# base-6u-custom-8535.net
KiCad netlist of a schematic drawn in EAGLE
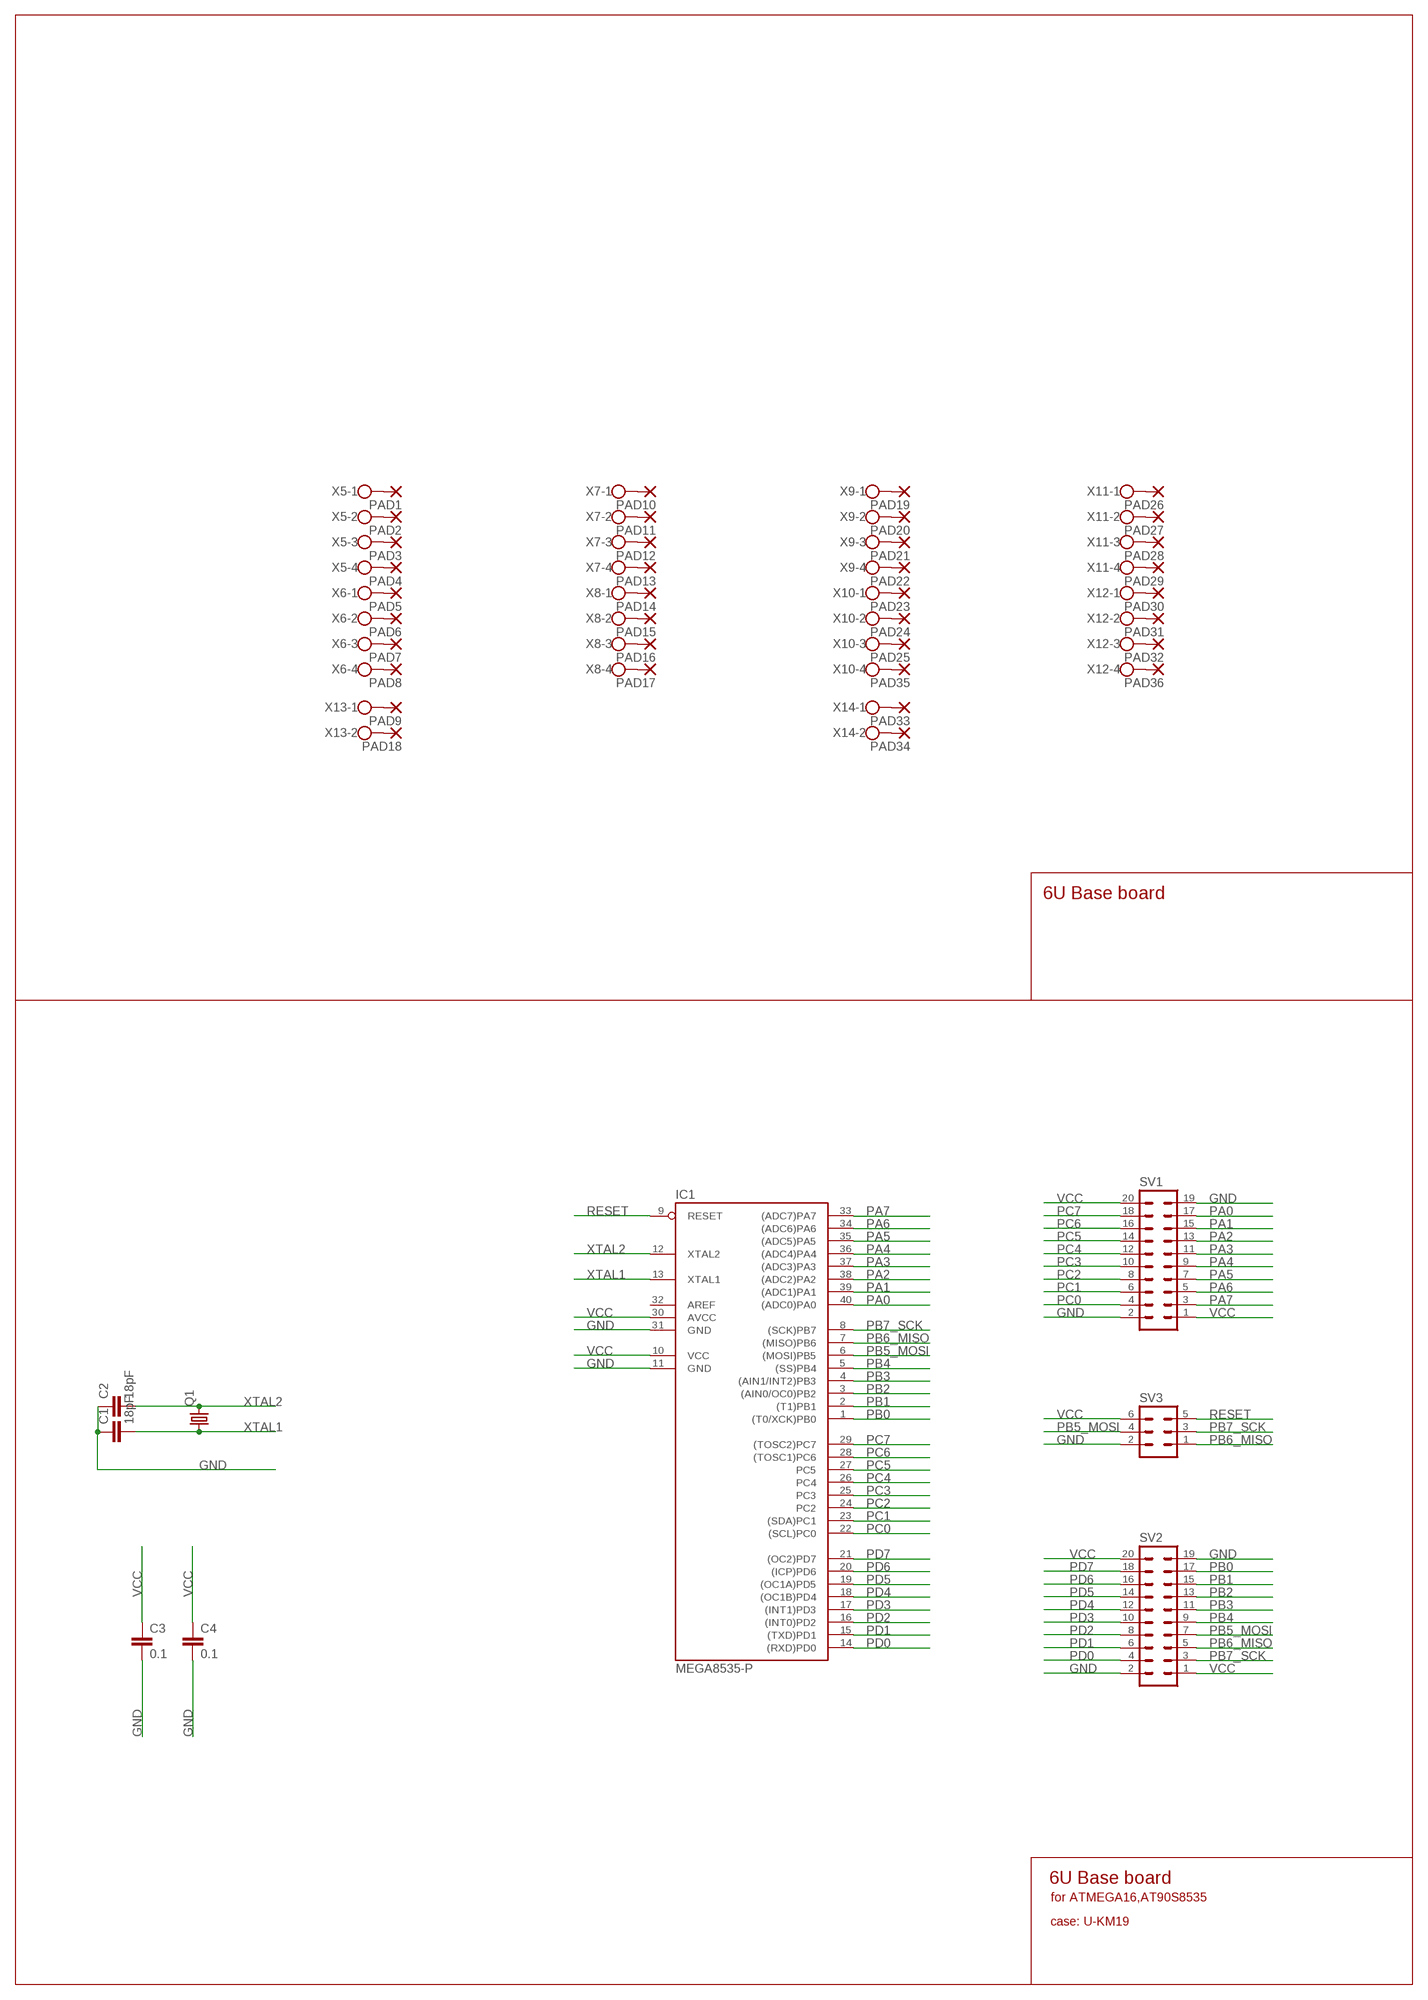
[diagram p0: schematic, sheet 1]

(export (version "E")
  (design (tool "Eeschema 10.0.6"))
  (components
    (comp (ref "C1")
      (value "18pF")
      (footprint "eagle-import:C0805")
      (libsource (lib "eagle-import") (part "C-EUC0805"))
    )
    (comp (ref "C2")
      (value "18pF")
      (footprint "eagle-import:C0805")
      (libsource (lib "eagle-import") (part "C-EUC0805"))
    )
    (comp (ref "C3")
      (value "0.1")
      (footprint "eagle-import:C0805")
      (libsource (lib "eagle-import") (part "C-EUC0805"))
    )
    (comp (ref "C4")
      (value "0.1")
      (footprint "eagle-import:C0805")
      (libsource (lib "eagle-import") (part "C-EUC0805"))
    )
    (comp (ref "IC1")
      (value "MEGA8535-P")
      (footprint "eagle-import:DIL40")
      (fields (field (name "MPN") "ATMEGA8535-16PU"))
      (libsource (lib "eagle-import") (part "MEGA8535-P"))
    )
    (comp (ref "PAD1")
      (value "2,54/0,8")
      (footprint "eagle-import:2,54_0,8")
      (libsource (lib "eagle-import") (part "2,54/0,8"))
    )
    (comp (ref "PAD2")
      (value "2,54/0,8")
      (footprint "eagle-import:2,54_0,8")
      (libsource (lib "eagle-import") (part "2,54/0,8"))
    )
    (comp (ref "PAD3")
      (value "2,54/0,8")
      (footprint "eagle-import:2,54_0,8")
      (libsource (lib "eagle-import") (part "2,54/0,8"))
    )
    (comp (ref "PAD4")
      (value "2,54/0,8")
      (footprint "eagle-import:2,54_0,8")
      (libsource (lib "eagle-import") (part "2,54/0,8"))
    )
    (comp (ref "PAD5")
      (value "2,54/0,8")
      (footprint "eagle-import:2,54_0,8")
      (libsource (lib "eagle-import") (part "2,54/0,8"))
    )
    (comp (ref "PAD6")
      (value "2,54/0,8")
      (footprint "eagle-import:2,54_0,8")
      (libsource (lib "eagle-import") (part "2,54/0,8"))
    )
    (comp (ref "PAD7")
      (value "2,54/0,8")
      (footprint "eagle-import:2,54_0,8")
      (libsource (lib "eagle-import") (part "2,54/0,8"))
    )
    (comp (ref "PAD8")
      (value "2,54/0,8")
      (footprint "eagle-import:2,54_0,8")
      (libsource (lib "eagle-import") (part "2,54/0,8"))
    )
    (comp (ref "PAD9")
      (value "2,54/0,8")
      (footprint "eagle-import:2,54_0,8")
      (libsource (lib "eagle-import") (part "2,54/0,8"))
    )
    (comp (ref "PAD10")
      (value "2,54/0,8")
      (footprint "eagle-import:2,54_0,8")
      (libsource (lib "eagle-import") (part "2,54/0,8"))
    )
    (comp (ref "PAD11")
      (value "2,54/0,8")
      (footprint "eagle-import:2,54_0,8")
      (libsource (lib "eagle-import") (part "2,54/0,8"))
    )
    (comp (ref "PAD12")
      (value "2,54/0,8")
      (footprint "eagle-import:2,54_0,8")
      (libsource (lib "eagle-import") (part "2,54/0,8"))
    )
    (comp (ref "PAD13")
      (value "2,54/0,8")
      (footprint "eagle-import:2,54_0,8")
      (libsource (lib "eagle-import") (part "2,54/0,8"))
    )
    (comp (ref "PAD14")
      (value "2,54/0,8")
      (footprint "eagle-import:2,54_0,8")
      (libsource (lib "eagle-import") (part "2,54/0,8"))
    )
    (comp (ref "PAD15")
      (value "2,54/0,8")
      (footprint "eagle-import:2,54_0,8")
      (libsource (lib "eagle-import") (part "2,54/0,8"))
    )
    (comp (ref "PAD16")
      (value "2,54/0,8")
      (footprint "eagle-import:2,54_0,8")
      (libsource (lib "eagle-import") (part "2,54/0,8"))
    )
    (comp (ref "PAD17")
      (value "2,54/0,8")
      (footprint "eagle-import:2,54_0,8")
      (libsource (lib "eagle-import") (part "2,54/0,8"))
    )
    (comp (ref "PAD18")
      (value "2,54/0,8")
      (footprint "eagle-import:2,54_0,8")
      (libsource (lib "eagle-import") (part "2,54/0,8"))
    )
    (comp (ref "PAD19")
      (value "2,54/0,8")
      (footprint "eagle-import:2,54_0,8")
      (libsource (lib "eagle-import") (part "2,54/0,8"))
    )
    (comp (ref "PAD20")
      (value "2,54/0,8")
      (footprint "eagle-import:2,54_0,8")
      (libsource (lib "eagle-import") (part "2,54/0,8"))
    )
    (comp (ref "PAD21")
      (value "2,54/0,8")
      (footprint "eagle-import:2,54_0,8")
      (libsource (lib "eagle-import") (part "2,54/0,8"))
    )
    (comp (ref "PAD22")
      (value "2,54/0,8")
      (footprint "eagle-import:2,54_0,8")
      (libsource (lib "eagle-import") (part "2,54/0,8"))
    )
    (comp (ref "PAD23")
      (value "2,54/0,8")
      (footprint "eagle-import:2,54_0,8")
      (libsource (lib "eagle-import") (part "2,54/0,8"))
    )
    (comp (ref "PAD24")
      (value "2,54/0,8")
      (footprint "eagle-import:2,54_0,8")
      (libsource (lib "eagle-import") (part "2,54/0,8"))
    )
    (comp (ref "PAD25")
      (value "2,54/0,8")
      (footprint "eagle-import:2,54_0,8")
      (libsource (lib "eagle-import") (part "2,54/0,8"))
    )
    (comp (ref "PAD26")
      (value "2,54/0,8")
      (footprint "eagle-import:2,54_0,8")
      (libsource (lib "eagle-import") (part "2,54/0,8"))
    )
    (comp (ref "PAD27")
      (value "2,54/0,8")
      (footprint "eagle-import:2,54_0,8")
      (libsource (lib "eagle-import") (part "2,54/0,8"))
    )
    (comp (ref "PAD28")
      (value "2,54/0,8")
      (footprint "eagle-import:2,54_0,8")
      (libsource (lib "eagle-import") (part "2,54/0,8"))
    )
    (comp (ref "PAD29")
      (value "2,54/0,8")
      (footprint "eagle-import:2,54_0,8")
      (libsource (lib "eagle-import") (part "2,54/0,8"))
    )
    (comp (ref "PAD30")
      (value "2,54/0,8")
      (footprint "eagle-import:2,54_0,8")
      (libsource (lib "eagle-import") (part "2,54/0,8"))
    )
    (comp (ref "PAD31")
      (value "2,54/0,8")
      (footprint "eagle-import:2,54_0,8")
      (libsource (lib "eagle-import") (part "2,54/0,8"))
    )
    (comp (ref "PAD32")
      (value "2,54/0,8")
      (footprint "eagle-import:2,54_0,8")
      (libsource (lib "eagle-import") (part "2,54/0,8"))
    )
    (comp (ref "PAD33")
      (value "2,54/0,8")
      (footprint "eagle-import:2,54_0,8")
      (libsource (lib "eagle-import") (part "2,54/0,8"))
    )
    (comp (ref "PAD34")
      (value "2,54/0,8")
      (footprint "eagle-import:2,54_0,8")
      (libsource (lib "eagle-import") (part "2,54/0,8"))
    )
    (comp (ref "PAD35")
      (value "2,54/0,8")
      (footprint "eagle-import:2,54_0,8")
      (libsource (lib "eagle-import") (part "2,54/0,8"))
    )
    (comp (ref "PAD36")
      (value "2,54/0,8")
      (footprint "eagle-import:2,54_0,8")
      (libsource (lib "eagle-import") (part "2,54/0,8"))
    )
    (comp (ref "Q1")
      (value "CRYSTALHC49S")
      (footprint "eagle-import:HC49_S")
      (libsource (lib "eagle-import") (part "CRYSTALHC49S"))
    )
    (comp (ref "SV1")
      (value "MA10-2")
      (footprint "eagle-import:MA10-2")
      (libsource (lib "eagle-import") (part "MA10-2"))
    )
    (comp (ref "SV2")
      (value "MA10-2")
      (footprint "eagle-import:MA10-2")
      (libsource (lib "eagle-import") (part "MA10-2"))
    )
    (comp (ref "SV3")
      (value "MA03-2")
      (footprint "eagle-import:MA03-2")
      (libsource (lib "eagle-import") (part "MA03-2"))
    )
    (comp (ref "X5")
      (value "W237-4")
      (footprint "eagle-import:W237-4")
      (libsource (lib "eagle-import") (part "W237-4"))
    )
    (comp (ref "X6")
      (value "W237-4")
      (footprint "eagle-import:W237-4")
      (libsource (lib "eagle-import") (part "W237-4"))
    )
    (comp (ref "X7")
      (value "W237-4")
      (footprint "eagle-import:W237-4")
      (libsource (lib "eagle-import") (part "W237-4"))
    )
    (comp (ref "X8")
      (value "W237-4")
      (footprint "eagle-import:W237-4")
      (libsource (lib "eagle-import") (part "W237-4"))
    )
    (comp (ref "X9")
      (value "W237-4")
      (footprint "eagle-import:W237-4")
      (libsource (lib "eagle-import") (part "W237-4"))
    )
    (comp (ref "X10")
      (value "W237-4")
      (footprint "eagle-import:W237-4")
      (libsource (lib "eagle-import") (part "W237-4"))
    )
    (comp (ref "X11")
      (value "W237-4")
      (footprint "eagle-import:W237-4")
      (libsource (lib "eagle-import") (part "W237-4"))
    )
    (comp (ref "X12")
      (value "W237-4")
      (footprint "eagle-import:W237-4")
      (libsource (lib "eagle-import") (part "W237-4"))
    )
    (comp (ref "X13")
      (value "W237-102")
      (footprint "eagle-import:W237-102")
      (fields (field (name "MPN") "237-102"))
      (libsource (lib "eagle-import") (part "W237-102"))
    )
    (comp (ref "X14")
      (value "W237-102")
      (footprint "eagle-import:W237-102")
      (fields (field (name "MPN") "237-102"))
      (libsource (lib "eagle-import") (part "W237-102"))
    )
  )
  (nets
    (net (code "1") (name "/GND") (class "Default")
      (node (ref "C1") (pin "1") (pinfunction "1_1") (pintype "passive"))
      (node (ref "C2") (pin "1") (pinfunction "1_1") (pintype "passive"))
      (node (ref "C3") (pin "2") (pinfunction "2_2") (pintype "passive"))
      (node (ref "C4") (pin "2") (pinfunction "2_2") (pintype "passive"))
      (node (ref "IC1") (pin "11") (pinfunction "GND_11") (pintype "power_in"))
      (node (ref "IC1") (pin "31") (pinfunction "GND_31") (pintype "power_in"))
      (node (ref "SV1") (pin "19") (pinfunction "19_19") (pintype "passive"))
      (node (ref "SV1") (pin "2") (pinfunction "2_2") (pintype "passive"))
      (node (ref "SV2") (pin "19") (pinfunction "19_19") (pintype "passive"))
      (node (ref "SV2") (pin "2") (pinfunction "2_2") (pintype "passive"))
      (node (ref "SV3") (pin "2") (pinfunction "2_2") (pintype "passive"))
    )
    (net (code "2") (name "/PA0") (class "Default")
      (node (ref "IC1") (pin "40") (pinfunction "(ADC0)PA0_40") (pintype "bidirectional"))
      (node (ref "SV1") (pin "17") (pinfunction "17_17") (pintype "passive"))
    )
    (net (code "3") (name "/PA1") (class "Default")
      (node (ref "IC1") (pin "39") (pinfunction "(ADC1)PA1_39") (pintype "bidirectional"))
      (node (ref "SV1") (pin "15") (pinfunction "15_15") (pintype "passive"))
    )
    (net (code "4") (name "/PA2") (class "Default")
      (node (ref "IC1") (pin "38") (pinfunction "(ADC2)PA2_38") (pintype "bidirectional"))
      (node (ref "SV1") (pin "13") (pinfunction "13_13") (pintype "passive"))
    )
    (net (code "5") (name "/PA3") (class "Default")
      (node (ref "IC1") (pin "37") (pinfunction "(ADC3)PA3_37") (pintype "bidirectional"))
      (node (ref "SV1") (pin "11") (pinfunction "11_11") (pintype "passive"))
    )
    (net (code "6") (name "/PA4") (class "Default")
      (node (ref "IC1") (pin "36") (pinfunction "(ADC4)PA4_36") (pintype "bidirectional"))
      (node (ref "SV1") (pin "9") (pinfunction "9_9") (pintype "passive"))
    )
    (net (code "7") (name "/PA5") (class "Default")
      (node (ref "IC1") (pin "35") (pinfunction "(ADC5)PA5_35") (pintype "bidirectional"))
      (node (ref "SV1") (pin "7") (pinfunction "7_7") (pintype "passive"))
    )
    (net (code "8") (name "/PA6") (class "Default")
      (node (ref "IC1") (pin "34") (pinfunction "(ADC6)PA6_34") (pintype "bidirectional"))
      (node (ref "SV1") (pin "5") (pinfunction "5_5") (pintype "passive"))
    )
    (net (code "9") (name "/PA7") (class "Default")
      (node (ref "IC1") (pin "33") (pinfunction "(ADC7)PA7_33") (pintype "bidirectional"))
      (node (ref "SV1") (pin "3") (pinfunction "3_3") (pintype "passive"))
    )
    (net (code "10") (name "/PB0") (class "Default")
      (node (ref "IC1") (pin "1") (pinfunction "(T0/XCK)PB0_1") (pintype "bidirectional"))
      (node (ref "SV2") (pin "17") (pinfunction "17_17") (pintype "passive"))
    )
    (net (code "11") (name "/PB1") (class "Default")
      (node (ref "IC1") (pin "2") (pinfunction "(T1)PB1_2") (pintype "bidirectional"))
      (node (ref "SV2") (pin "15") (pinfunction "15_15") (pintype "passive"))
    )
    (net (code "12") (name "/PB2") (class "Default")
      (node (ref "IC1") (pin "3") (pinfunction "(AIN0/OC0)PB2_3") (pintype "bidirectional"))
      (node (ref "SV2") (pin "13") (pinfunction "13_13") (pintype "passive"))
    )
    (net (code "13") (name "/PB3") (class "Default")
      (node (ref "IC1") (pin "4") (pinfunction "(AIN1/INT2)PB3_4") (pintype "bidirectional"))
      (node (ref "SV2") (pin "11") (pinfunction "11_11") (pintype "passive"))
    )
    (net (code "14") (name "/PB4") (class "Default")
      (node (ref "IC1") (pin "5") (pinfunction "(SS)PB4_5") (pintype "bidirectional"))
      (node (ref "SV2") (pin "9") (pinfunction "9_9") (pintype "passive"))
    )
    (net (code "15") (name "/PB5_MOSI") (class "Default")
      (node (ref "IC1") (pin "6") (pinfunction "(MOSI)PB5_6") (pintype "bidirectional"))
      (node (ref "SV2") (pin "7") (pinfunction "7_7") (pintype "passive"))
      (node (ref "SV3") (pin "4") (pinfunction "4_4") (pintype "passive"))
    )
    (net (code "16") (name "/PB6_MISO") (class "Default")
      (node (ref "IC1") (pin "7") (pinfunction "(MISO)PB6_7") (pintype "bidirectional"))
      (node (ref "SV2") (pin "5") (pinfunction "5_5") (pintype "passive"))
      (node (ref "SV3") (pin "1") (pinfunction "1_1") (pintype "passive"))
    )
    (net (code "17") (name "/PB7_SCK") (class "Default")
      (node (ref "IC1") (pin "8") (pinfunction "(SCK)PB7_8") (pintype "bidirectional"))
      (node (ref "SV2") (pin "3") (pinfunction "3_3") (pintype "passive"))
      (node (ref "SV3") (pin "3") (pinfunction "3_3") (pintype "passive"))
    )
    (net (code "18") (name "/PC0") (class "Default")
      (node (ref "IC1") (pin "22") (pinfunction "(SCL)PC0_22") (pintype "bidirectional"))
      (node (ref "SV1") (pin "4") (pinfunction "4_4") (pintype "passive"))
    )
    (net (code "19") (name "/PC1") (class "Default")
      (node (ref "IC1") (pin "23") (pinfunction "(SDA)PC1_23") (pintype "bidirectional"))
      (node (ref "SV1") (pin "6") (pinfunction "6_6") (pintype "passive"))
    )
    (net (code "20") (name "/PC2") (class "Default")
      (node (ref "IC1") (pin "24") (pinfunction "PC2_24") (pintype "bidirectional"))
      (node (ref "SV1") (pin "8") (pinfunction "8_8") (pintype "passive"))
    )
    (net (code "21") (name "/PC3") (class "Default")
      (node (ref "IC1") (pin "25") (pinfunction "PC3_25") (pintype "bidirectional"))
      (node (ref "SV1") (pin "10") (pinfunction "10_10") (pintype "passive"))
    )
    (net (code "22") (name "/PC4") (class "Default")
      (node (ref "IC1") (pin "26") (pinfunction "PC4_26") (pintype "bidirectional"))
      (node (ref "SV1") (pin "12") (pinfunction "12_12") (pintype "passive"))
    )
    (net (code "23") (name "/PC5") (class "Default")
      (node (ref "IC1") (pin "27") (pinfunction "PC5_27") (pintype "bidirectional"))
      (node (ref "SV1") (pin "14") (pinfunction "14_14") (pintype "passive"))
    )
    (net (code "24") (name "/PC6") (class "Default")
      (node (ref "IC1") (pin "28") (pinfunction "(TOSC1)PC6_28") (pintype "bidirectional"))
      (node (ref "SV1") (pin "16") (pinfunction "16_16") (pintype "passive"))
    )
    (net (code "25") (name "/PC7") (class "Default")
      (node (ref "IC1") (pin "29") (pinfunction "(TOSC2)PC7_29") (pintype "bidirectional"))
      (node (ref "SV1") (pin "18") (pinfunction "18_18") (pintype "passive"))
    )
    (net (code "26") (name "/PD0") (class "Default")
      (node (ref "IC1") (pin "14") (pinfunction "(RXD)PD0_14") (pintype "bidirectional"))
      (node (ref "SV2") (pin "4") (pinfunction "4_4") (pintype "passive"))
    )
    (net (code "27") (name "/PD1") (class "Default")
      (node (ref "IC1") (pin "15") (pinfunction "(TXD)PD1_15") (pintype "bidirectional"))
      (node (ref "SV2") (pin "6") (pinfunction "6_6") (pintype "passive"))
    )
    (net (code "28") (name "/PD2") (class "Default")
      (node (ref "IC1") (pin "16") (pinfunction "(INT0)PD2_16") (pintype "bidirectional"))
      (node (ref "SV2") (pin "8") (pinfunction "8_8") (pintype "passive"))
    )
    (net (code "29") (name "/PD3") (class "Default")
      (node (ref "IC1") (pin "17") (pinfunction "(INT1)PD3_17") (pintype "bidirectional"))
      (node (ref "SV2") (pin "10") (pinfunction "10_10") (pintype "passive"))
    )
    (net (code "30") (name "/PD4") (class "Default")
      (node (ref "IC1") (pin "18") (pinfunction "(OC1B)PD4_18") (pintype "bidirectional"))
      (node (ref "SV2") (pin "12") (pinfunction "12_12") (pintype "passive"))
    )
    (net (code "31") (name "/PD5") (class "Default")
      (node (ref "IC1") (pin "19") (pinfunction "(OC1A)PD5_19") (pintype "bidirectional"))
      (node (ref "SV2") (pin "14") (pinfunction "14_14") (pintype "passive"))
    )
    (net (code "32") (name "/PD6") (class "Default")
      (node (ref "IC1") (pin "20") (pinfunction "(ICP)PD6_20") (pintype "bidirectional"))
      (node (ref "SV2") (pin "16") (pinfunction "16_16") (pintype "passive"))
    )
    (net (code "33") (name "/PD7") (class "Default")
      (node (ref "IC1") (pin "21") (pinfunction "(OC2)PD7_21") (pintype "bidirectional"))
      (node (ref "SV2") (pin "18") (pinfunction "18_18") (pintype "passive"))
    )
    (net (code "34") (name "/RESET") (class "Default")
      (node (ref "IC1") (pin "9") (pinfunction "RESET_9") (pintype "input"))
      (node (ref "SV3") (pin "5") (pinfunction "5_5") (pintype "passive"))
    )
    (net (code "35") (name "/VCC") (class "Default")
      (node (ref "C3") (pin "1") (pinfunction "1_1") (pintype "passive"))
      (node (ref "C4") (pin "1") (pinfunction "1_1") (pintype "passive"))
      (node (ref "IC1") (pin "10") (pinfunction "VCC_10") (pintype "power_in"))
      (node (ref "IC1") (pin "30") (pinfunction "AVCC_30") (pintype "power_in"))
      (node (ref "SV1") (pin "1") (pinfunction "1_1") (pintype "passive"))
      (node (ref "SV1") (pin "20") (pinfunction "20_20") (pintype "passive"))
      (node (ref "SV2") (pin "1") (pinfunction "1_1") (pintype "passive"))
      (node (ref "SV2") (pin "20") (pinfunction "20_20") (pintype "passive"))
      (node (ref "SV3") (pin "6") (pinfunction "6_6") (pintype "passive"))
    )
    (net (code "36") (name "/XTAL1") (class "Default")
      (node (ref "C1") (pin "2") (pinfunction "2_2") (pintype "passive"))
      (node (ref "IC1") (pin "13") (pinfunction "XTAL1_13") (pintype "bidirectional"))
      (node (ref "Q1") (pin "1") (pinfunction "1_1") (pintype "passive"))
    )
    (net (code "37") (name "/XTAL2") (class "Default")
      (node (ref "C2") (pin "2") (pinfunction "2_2") (pintype "passive"))
      (node (ref "IC1") (pin "12") (pinfunction "XTAL2_12") (pintype "bidirectional"))
      (node (ref "Q1") (pin "2") (pinfunction "2_2") (pintype "passive"))
    )
    (net (code "38") (name "Net-(PAD1-P)") (class "Default")
      (node (ref "PAD1") (pin "1") (pinfunction "P_1") (pintype "passive"))
      (node (ref "X5") (pin "1") (pinfunction "KL_1") (pintype "passive"))
    )
    (net (code "39") (name "Net-(PAD2-P)") (class "Default")
      (node (ref "PAD2") (pin "1") (pinfunction "P_1") (pintype "passive"))
      (node (ref "X5") (pin "2") (pinfunction "KL_2") (pintype "passive"))
    )
    (net (code "40") (name "Net-(PAD3-P)") (class "Default")
      (node (ref "PAD3") (pin "1") (pinfunction "P_1") (pintype "passive"))
      (node (ref "X5") (pin "3") (pinfunction "KL_3") (pintype "passive"))
    )
    (net (code "41") (name "Net-(PAD4-P)") (class "Default")
      (node (ref "PAD4") (pin "1") (pinfunction "P_1") (pintype "passive"))
      (node (ref "X5") (pin "4") (pinfunction "KL_4") (pintype "passive"))
    )
    (net (code "42") (name "Net-(PAD5-P)") (class "Default")
      (node (ref "PAD5") (pin "1") (pinfunction "P_1") (pintype "passive"))
      (node (ref "X6") (pin "1") (pinfunction "KL_1") (pintype "passive"))
    )
    (net (code "43") (name "Net-(PAD6-P)") (class "Default")
      (node (ref "PAD6") (pin "1") (pinfunction "P_1") (pintype "passive"))
      (node (ref "X6") (pin "2") (pinfunction "KL_2") (pintype "passive"))
    )
    (net (code "44") (name "Net-(PAD7-P)") (class "Default")
      (node (ref "PAD7") (pin "1") (pinfunction "P_1") (pintype "passive"))
      (node (ref "X6") (pin "3") (pinfunction "KL_3") (pintype "passive"))
    )
    (net (code "45") (name "Net-(PAD8-P)") (class "Default")
      (node (ref "PAD8") (pin "1") (pinfunction "P_1") (pintype "passive"))
      (node (ref "X6") (pin "4") (pinfunction "KL_4") (pintype "passive"))
    )
    (net (code "46") (name "Net-(PAD9-P)") (class "Default")
      (node (ref "PAD9") (pin "1") (pinfunction "P_1") (pintype "passive"))
      (node (ref "X13") (pin "1") (pinfunction "KL_1") (pintype "passive"))
    )
    (net (code "47") (name "Net-(PAD10-P)") (class "Default")
      (node (ref "PAD10") (pin "1") (pinfunction "P_1") (pintype "passive"))
      (node (ref "X7") (pin "1") (pinfunction "KL_1") (pintype "passive"))
    )
    (net (code "48") (name "Net-(PAD11-P)") (class "Default")
      (node (ref "PAD11") (pin "1") (pinfunction "P_1") (pintype "passive"))
      (node (ref "X7") (pin "2") (pinfunction "KL_2") (pintype "passive"))
    )
    (net (code "49") (name "Net-(PAD12-P)") (class "Default")
      (node (ref "PAD12") (pin "1") (pinfunction "P_1") (pintype "passive"))
      (node (ref "X7") (pin "3") (pinfunction "KL_3") (pintype "passive"))
    )
    (net (code "50") (name "Net-(PAD13-P)") (class "Default")
      (node (ref "PAD13") (pin "1") (pinfunction "P_1") (pintype "passive"))
      (node (ref "X7") (pin "4") (pinfunction "KL_4") (pintype "passive"))
    )
    (net (code "51") (name "Net-(PAD14-P)") (class "Default")
      (node (ref "PAD14") (pin "1") (pinfunction "P_1") (pintype "passive"))
      (node (ref "X8") (pin "1") (pinfunction "KL_1") (pintype "passive"))
    )
    (net (code "52") (name "Net-(PAD15-P)") (class "Default")
      (node (ref "PAD15") (pin "1") (pinfunction "P_1") (pintype "passive"))
      (node (ref "X8") (pin "2") (pinfunction "KL_2") (pintype "passive"))
    )
    (net (code "53") (name "Net-(PAD16-P)") (class "Default")
      (node (ref "PAD16") (pin "1") (pinfunction "P_1") (pintype "passive"))
      (node (ref "X8") (pin "3") (pinfunction "KL_3") (pintype "passive"))
    )
    (net (code "54") (name "Net-(PAD17-P)") (class "Default")
      (node (ref "PAD17") (pin "1") (pinfunction "P_1") (pintype "passive"))
      (node (ref "X8") (pin "4") (pinfunction "KL_4") (pintype "passive"))
    )
    (net (code "55") (name "Net-(PAD18-P)") (class "Default")
      (node (ref "PAD18") (pin "1") (pinfunction "P_1") (pintype "passive"))
      (node (ref "X13") (pin "2") (pinfunction "KL_2") (pintype "passive"))
    )
    (net (code "56") (name "Net-(PAD19-P)") (class "Default")
      (node (ref "PAD19") (pin "1") (pinfunction "P_1") (pintype "passive"))
      (node (ref "X9") (pin "1") (pinfunction "KL_1") (pintype "passive"))
    )
    (net (code "57") (name "Net-(PAD20-P)") (class "Default")
      (node (ref "PAD20") (pin "1") (pinfunction "P_1") (pintype "passive"))
      (node (ref "X9") (pin "2") (pinfunction "KL_2") (pintype "passive"))
    )
    (net (code "58") (name "Net-(PAD21-P)") (class "Default")
      (node (ref "PAD21") (pin "1") (pinfunction "P_1") (pintype "passive"))
      (node (ref "X9") (pin "3") (pinfunction "KL_3") (pintype "passive"))
    )
    (net (code "59") (name "Net-(PAD22-P)") (class "Default")
      (node (ref "PAD22") (pin "1") (pinfunction "P_1") (pintype "passive"))
      (node (ref "X9") (pin "4") (pinfunction "KL_4") (pintype "passive"))
    )
    (net (code "60") (name "Net-(PAD23-P)") (class "Default")
      (node (ref "PAD23") (pin "1") (pinfunction "P_1") (pintype "passive"))
      (node (ref "X10") (pin "1") (pinfunction "KL_1") (pintype "passive"))
    )
    (net (code "61") (name "Net-(PAD24-P)") (class "Default")
      (node (ref "PAD24") (pin "1") (pinfunction "P_1") (pintype "passive"))
      (node (ref "X10") (pin "2") (pinfunction "KL_2") (pintype "passive"))
    )
    (net (code "62") (name "Net-(PAD25-P)") (class "Default")
      (node (ref "PAD25") (pin "1") (pinfunction "P_1") (pintype "passive"))
      (node (ref "X10") (pin "3") (pinfunction "KL_3") (pintype "passive"))
    )
    (net (code "63") (name "Net-(PAD26-P)") (class "Default")
      (node (ref "PAD26") (pin "1") (pinfunction "P_1") (pintype "passive"))
      (node (ref "X11") (pin "1") (pinfunction "KL_1") (pintype "passive"))
    )
    (net (code "64") (name "Net-(PAD27-P)") (class "Default")
      (node (ref "PAD27") (pin "1") (pinfunction "P_1") (pintype "passive"))
      (node (ref "X11") (pin "2") (pinfunction "KL_2") (pintype "passive"))
    )
    (net (code "65") (name "Net-(PAD28-P)") (class "Default")
      (node (ref "PAD28") (pin "1") (pinfunction "P_1") (pintype "passive"))
      (node (ref "X11") (pin "3") (pinfunction "KL_3") (pintype "passive"))
    )
    (net (code "66") (name "Net-(PAD29-P)") (class "Default")
      (node (ref "PAD29") (pin "1") (pinfunction "P_1") (pintype "passive"))
      (node (ref "X11") (pin "4") (pinfunction "KL_4") (pintype "passive"))
    )
    (net (code "67") (name "Net-(PAD30-P)") (class "Default")
      (node (ref "PAD30") (pin "1") (pinfunction "P_1") (pintype "passive"))
      (node (ref "X12") (pin "1") (pinfunction "KL_1") (pintype "passive"))
    )
    (net (code "68") (name "Net-(PAD31-P)") (class "Default")
      (node (ref "PAD31") (pin "1") (pinfunction "P_1") (pintype "passive"))
      (node (ref "X12") (pin "2") (pinfunction "KL_2") (pintype "passive"))
    )
    (net (code "69") (name "Net-(PAD32-P)") (class "Default")
      (node (ref "PAD32") (pin "1") (pinfunction "P_1") (pintype "passive"))
      (node (ref "X12") (pin "3") (pinfunction "KL_3") (pintype "passive"))
    )
    (net (code "70") (name "Net-(PAD33-P)") (class "Default")
      (node (ref "PAD33") (pin "1") (pinfunction "P_1") (pintype "passive"))
      (node (ref "X14") (pin "1") (pinfunction "KL_1") (pintype "passive"))
    )
    (net (code "71") (name "Net-(PAD34-P)") (class "Default")
      (node (ref "PAD34") (pin "1") (pinfunction "P_1") (pintype "passive"))
      (node (ref "X14") (pin "2") (pinfunction "KL_2") (pintype "passive"))
    )
    (net (code "72") (name "Net-(PAD35-P)") (class "Default")
      (node (ref "PAD35") (pin "1") (pinfunction "P_1") (pintype "passive"))
      (node (ref "X10") (pin "4") (pinfunction "KL_4") (pintype "passive"))
    )
    (net (code "73") (name "Net-(PAD36-P)") (class "Default")
      (node (ref "PAD36") (pin "1") (pinfunction "P_1") (pintype "passive"))
      (node (ref "X12") (pin "4") (pinfunction "KL_4") (pintype "passive"))
    )
    (net (code "74") (name "unconnected-(IC1-AREF-Pad32)") (class "Default")
      (node (ref "IC1") (pin "32") (pinfunction "AREF_32") (pintype "passive"))
    )
  )
)
